# C-08_SODIMM.net
KiCad netlist of a schematic drawn in Altium Designer
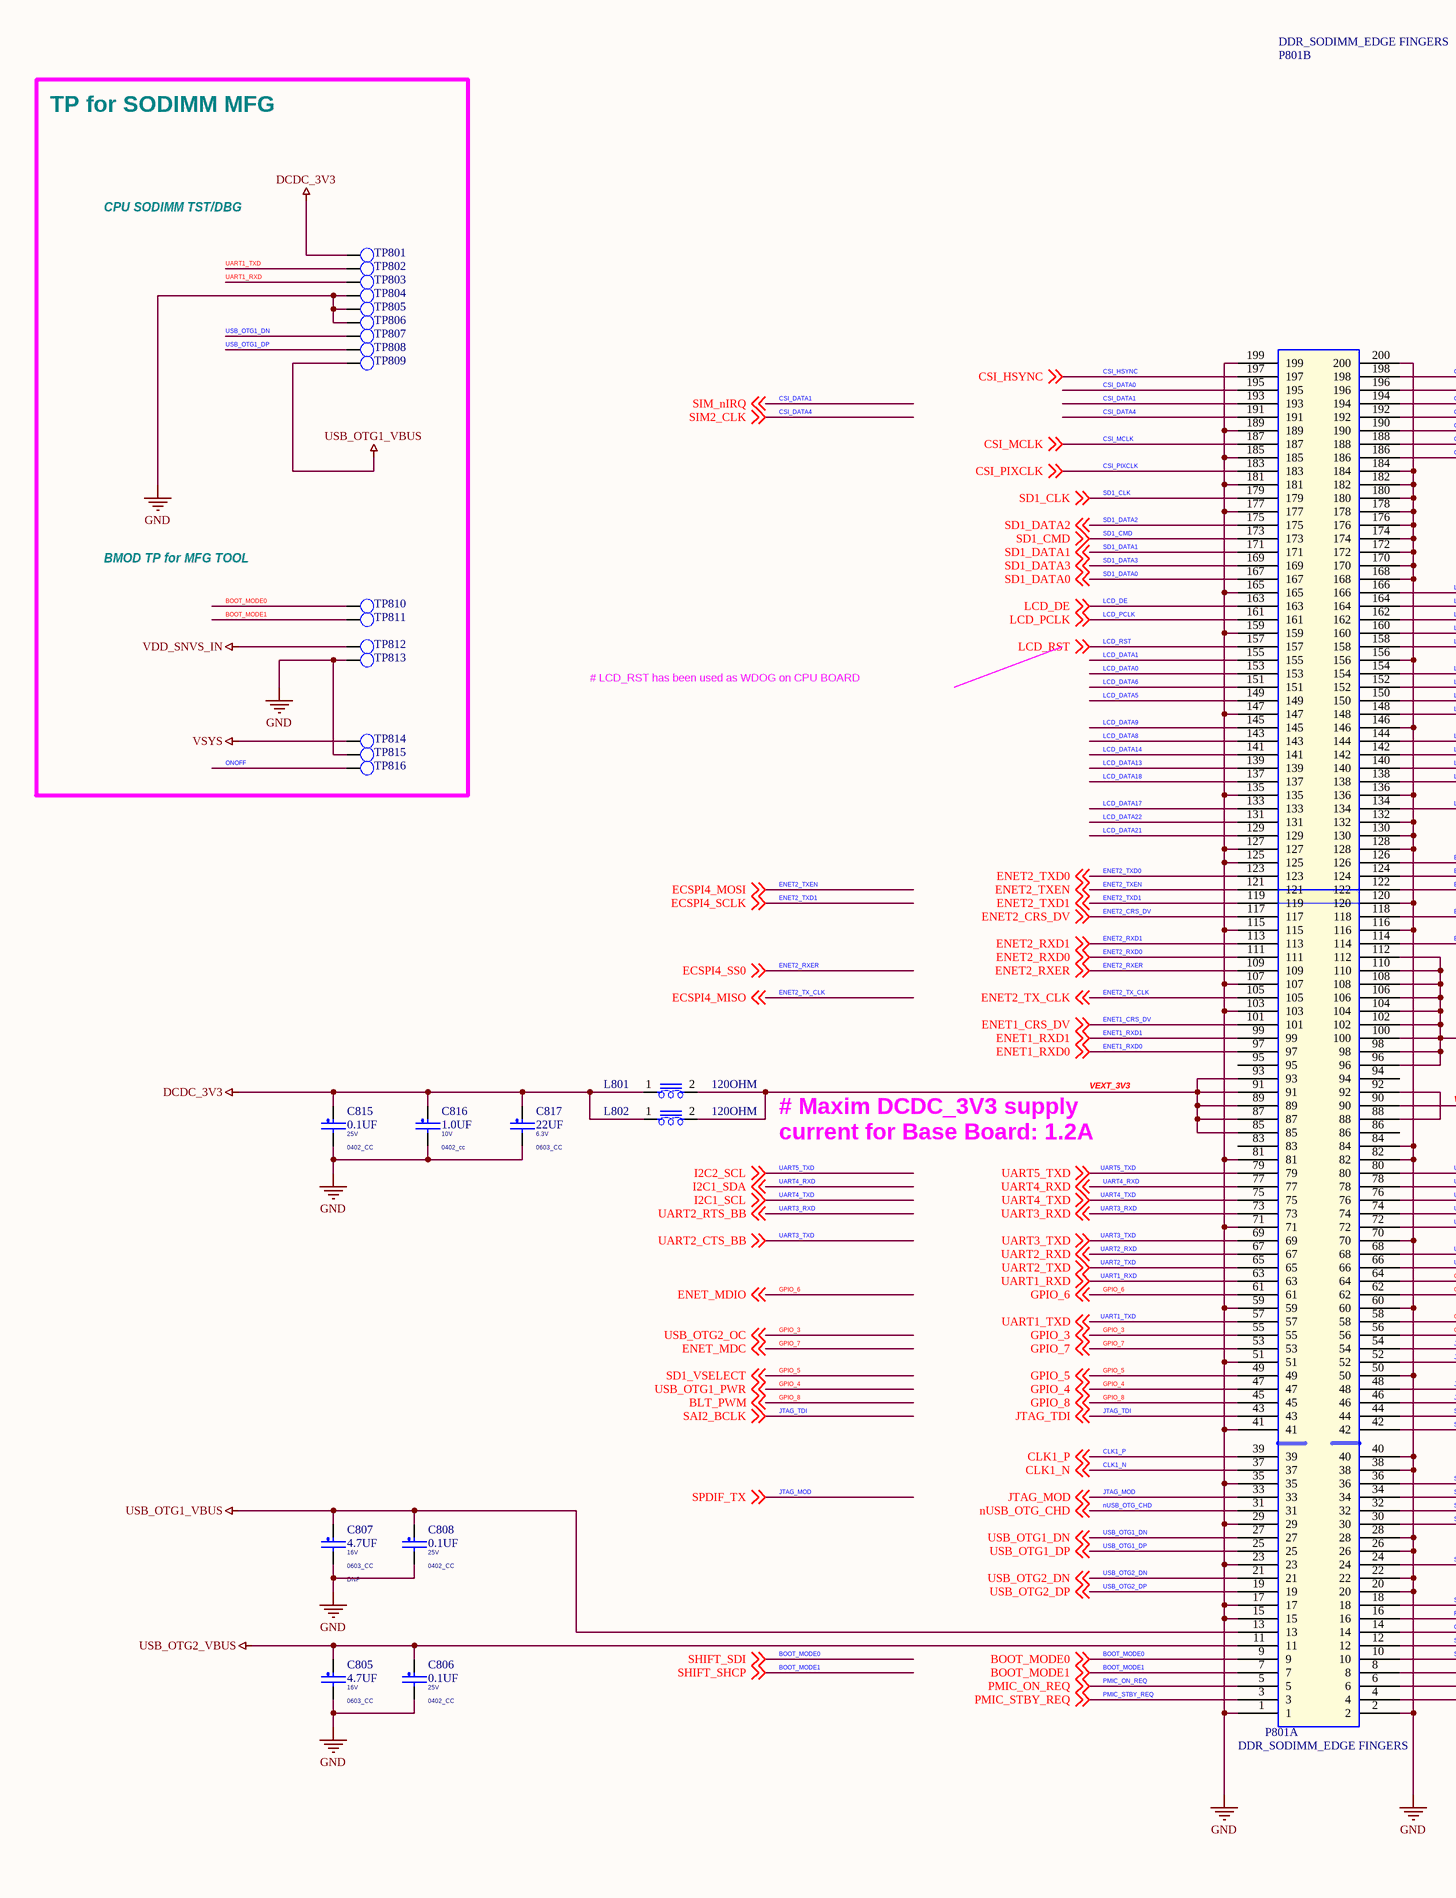
[diagram p0: C-08 SODIMM.SchDoc, left]
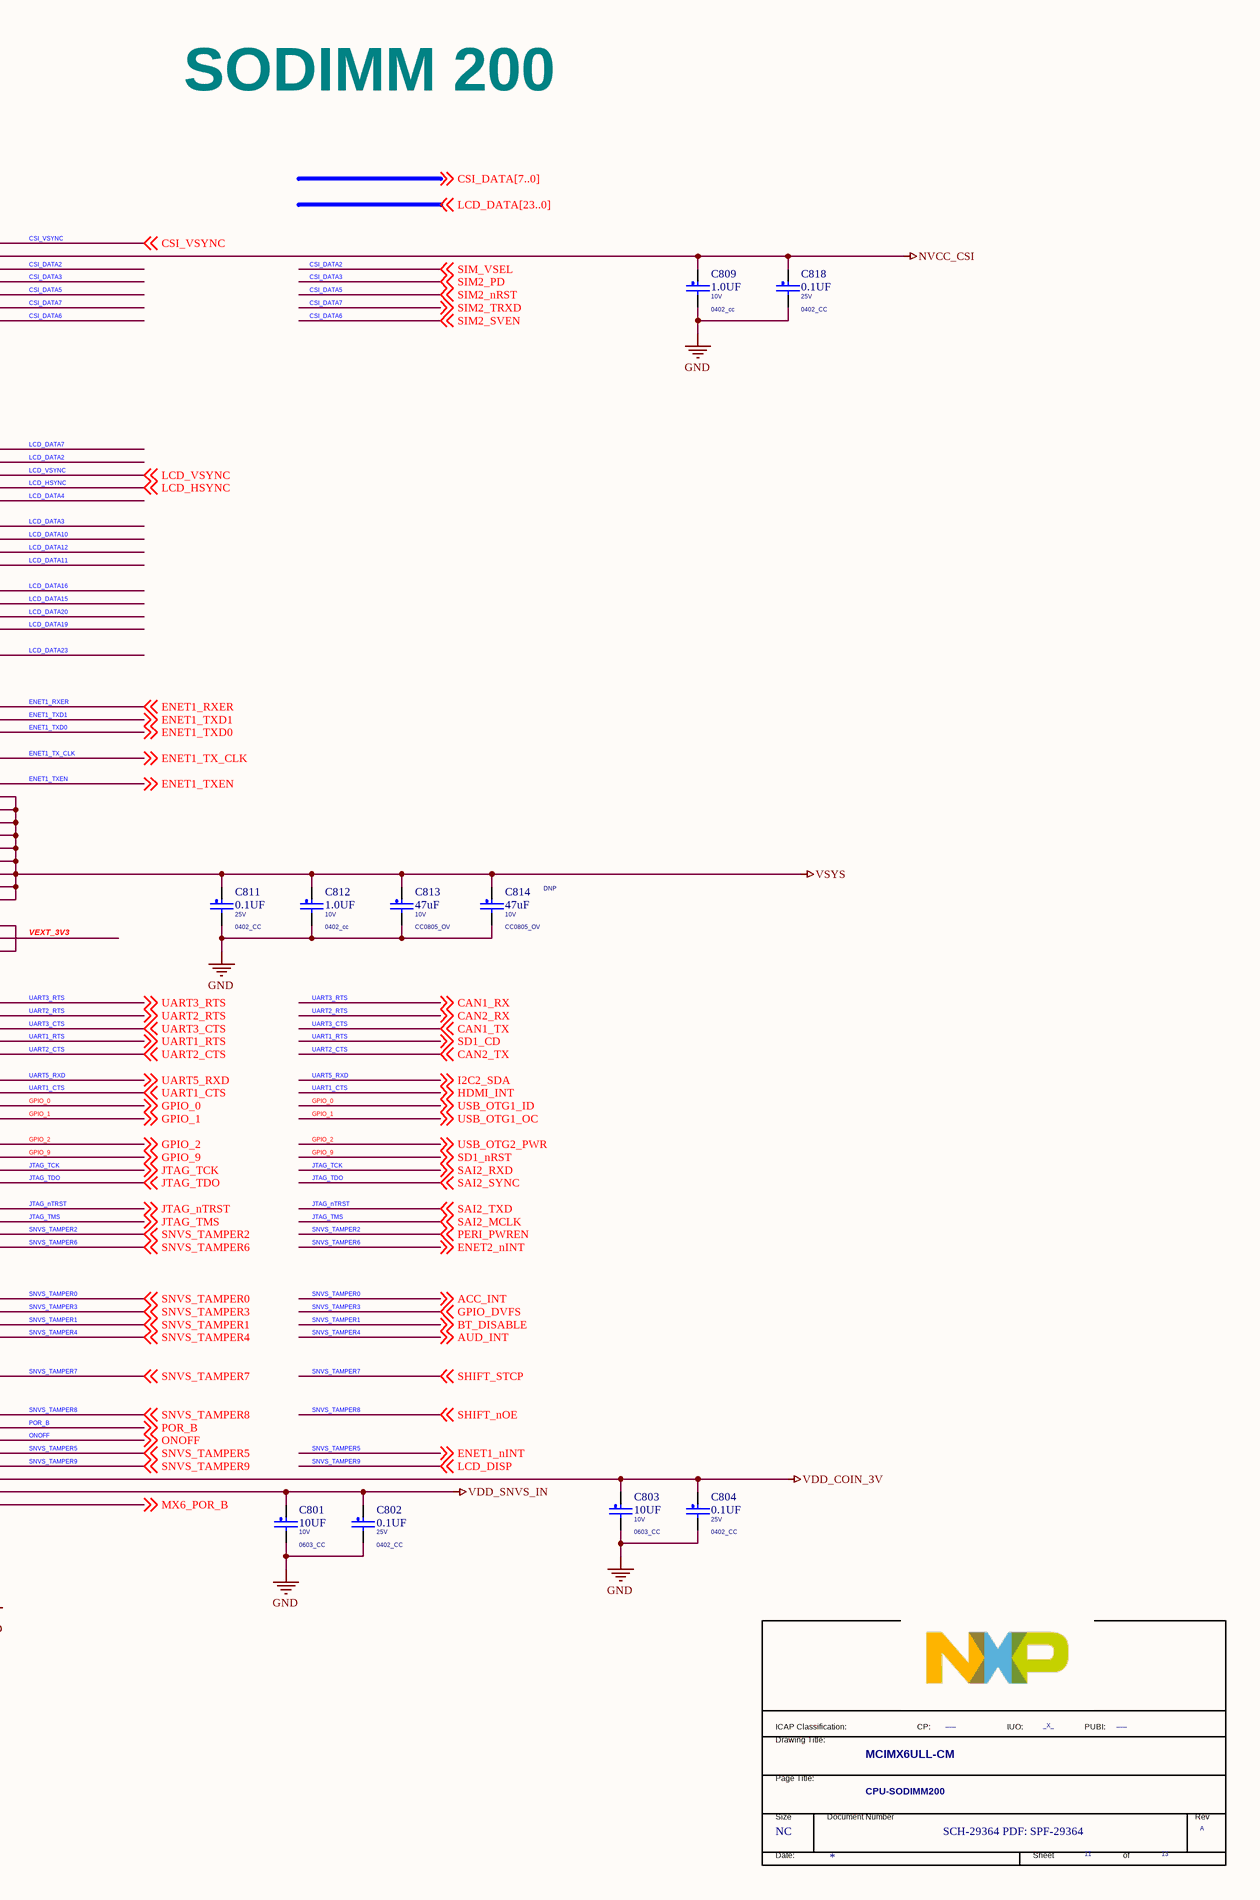
[diagram p1: C-08 SODIMM.SchDoc, right]

(export (version "E")
  (design (tool "Eeschema 10.0.6"))
  (components
    (comp (ref "*")
      (value "TitleBlock_FS")
      (fields
        (field (name "FIUO") "_X_")
        (field (name "PUBI") "___")
        (field (name "FCP") "___")
        (field (name "DOC") "SCH-29364 PDF: SPF-29364")
        (field (name "REVCODE") "A")
        (field (name "TITLE") "MCIMX6ULL-CM")
        (field (name "PAGE SIZE") "NC")
        (field (name "PAGE NUMBER") "11")
        (field (name "PAGE COUNT") "13")
        (field (name "PAGETITLE") "CPU-SODIMM200")
      )
      (libsource (lib "*") (part "TitleBlock_FS"))
    )
    (comp (ref "C801")
      (value "10UF")
      (footprint "C0603_H0.8mm_IPC_C")
      (description "CAP CER 10UF 10V 20% X5R 0603")
      (fields (field (name "VOLTAGE") "10V") (field (name "PCB FOOTPRINT") "0603_CC"))
      (libsource (lib "*") (part "CAP_NP"))
    )
    (comp (ref "C802")
      (value "0.1UF")
      (footprint "C0402_H0.5mm")
      (description "CAP CER 0.1UF 25V 10% X5R 0402")
      (fields
        (field (name "TOLERANCE") "10%")
        (field (name "VOLTAGE") "25V")
        (field (name "PCB FOOTPRINT") "0402_CC")
      )
      (libsource (lib "*") (part "CAP_NP"))
    )
    (comp (ref "C803")
      (value "10UF")
      (footprint "C0603_H0.8mm_IPC_C")
      (description "CAP CER 10UF 10V 20% X5R 0603")
      (fields (field (name "VOLTAGE") "10V") (field (name "PCB FOOTPRINT") "0603_CC"))
      (libsource (lib "*") (part "CAP_NP"))
    )
    (comp (ref "C804")
      (value "0.1UF")
      (footprint "C0402_H0.5mm")
      (description "CAP CER 0.1UF 25V 10% X5R 0402")
      (fields
        (field (name "TOLERANCE") "10%")
        (field (name "VOLTAGE") "25V")
        (field (name "PCB FOOTPRINT") "0402_CC")
      )
      (libsource (lib "*") (part "CAP_NP"))
    )
    (comp (ref "C805")
      (value "4.7UF")
      (footprint "C0603_H0.8mm_IPC_C")
      (description "CAP CER 4.7uF 16V 10% X5R 0603")
      (fields
        (field (name "TOLERANCE") "10%")
        (field (name "VOLTAGE") "16V")
        (field (name "PCB FOOTPRINT") "0603_CC")
      )
      (libsource (lib "*") (part "CAP_NP"))
    )
    (comp (ref "C806")
      (value "0.1UF")
      (footprint "C0402_H0.5mm")
      (description "CAP CER 0.1UF 25V 10% X5R 0402")
      (fields
        (field (name "TOLERANCE") "10%")
        (field (name "VOLTAGE") "25V")
        (field (name "PCB FOOTPRINT") "0402_CC")
      )
      (libsource (lib "*") (part "CAP_NP"))
    )
    (comp (ref "C807")
      (value "4.7UF")
      (footprint "C0603_H0.8mm_IPC_C")
      (description "CAP CER 4.7uF 16V 10% X5R 0603")
      (fields
        (field (name "PCB FOOTPRINT") "0603_CC")
        (field (name "VOLTAGE") "16V")
        (field (name "ASSY_OPT") "DNP")
        (field (name "TOLERANCE") "10%")
      )
      (libsource (lib "*") (part "CAP_NP"))
    )
    (comp (ref "C808")
      (value "0.1UF")
      (footprint "C0402_H0.5mm")
      (description "CAP CER 0.1UF 25V 10% X5R 0402")
      (fields
        (field (name "TOLERANCE") "10%")
        (field (name "VOLTAGE") "25V")
        (field (name "PCB FOOTPRINT") "0402_CC")
      )
      (libsource (lib "*") (part "CAP_NP"))
    )
    (comp (ref "C809")
      (value "1.0UF")
      (footprint "C0402_H0.5mm")
      (description "CAP CER 1.0UF 10V 10% X5R 0402")
      (fields (field (name "VOLTAGE") "10V") (field (name "PCB FOOTPRINT") "0402_cc"))
      (libsource (lib "*") (part "CAP_NP"))
    )
    (comp (ref "C811")
      (value "0.1UF")
      (footprint "C0402_H0.5mm")
      (description "CAP CER 0.1UF 25V 10% X5R 0402")
      (fields
        (field (name "VOLTAGE") "25V")
        (field (name "TOLERANCE") "10%")
        (field (name "PCB FOOTPRINT") "0402_CC")
      )
      (libsource (lib "*") (part "CAP_NP"))
    )
    (comp (ref "C812")
      (value "1.0UF")
      (footprint "C0402_H0.5mm")
      (description "CAP CER 1.0UF 10V 10% X5R 0402")
      (fields (field (name "VOLTAGE") "10V") (field (name "PCB FOOTPRINT") "0402_cc"))
      (libsource (lib "*") (part "CAP_NP"))
    )
    (comp (ref "C813")
      (value "47uF")
      (footprint "CC0805_OV")
      (description "CAP CER 47uF 10V 20% X5R 0805")
      (fields
        (field (name "VOLTAGE") "10V")
        (field (name "TOLERANCE") "20%")
        (field (name "PCB FOOTPRINT") "CC0805_OV")
      )
      (libsource (lib "*") (part "CAP_NP"))
    )
    (comp (ref "C814")
      (value "47uF")
      (footprint "CC0805_OV")
      (description "CAP CER 47uF 10V 20% X5R 0805")
      (fields
        (field (name "VOLTAGE") "10V")
        (field (name "ASSY_OPT") "DNP")
        (field (name "TOLERANCE") "20%")
        (field (name "PCB FOOTPRINT") "CC0805_OV")
      )
      (libsource (lib "*") (part "CAP_NP"))
    )
    (comp (ref "C815")
      (value "0.1UF")
      (footprint "C0402_H0.5mm")
      (description "CAP CER 0.1UF 25V 10% X5R 0402")
      (fields
        (field (name "VOLTAGE") "25V")
        (field (name "TOLERANCE") "10%")
        (field (name "PCB FOOTPRINT") "0402_CC")
      )
      (libsource (lib "*") (part "CAP_NP"))
    )
    (comp (ref "C816")
      (value "1.0UF")
      (footprint "C0402_H0.5mm")
      (description "CAP CER 1.0UF 10V 10% X5R 0402")
      (fields (field (name "VOLTAGE") "10V") (field (name "PCB FOOTPRINT") "0402_cc"))
      (libsource (lib "*") (part "CAP_NP"))
    )
    (comp (ref "C817")
      (value "22UF")
      (footprint "C0603_H0.8mm_IPC_C")
      (description "CAP CER 22UF 6.3V 20% X5R 0603")
      (fields
        (field (name "VOLTAGE") "6.3V")
        (field (name "TOLERANCE") "20%")
        (field (name "VOLTAGE RATING") "6.3V")
        (field (name "PCB FOOTPRINT") "0603_CC")
      )
      (libsource (lib "*") (part "CAP_NP"))
    )
    (comp (ref "C818")
      (value "0.1UF")
      (footprint "C0402_H0.5mm")
      (description "CAP CER 0.1UF 25V 10% X5R 0402")
      (fields
        (field (name "VOLTAGE") "25V")
        (field (name "TOLERANCE") "10%")
        (field (name "PCB FOOTPRINT") "0402_CC")
      )
      (libsource (lib "*") (part "CAP_NP"))
    )
    (comp (ref "L801")
      (value "120OHM")
      (footprint "0603_CC")
      (description "IND FER BEAD 120OHM@100MHZ 2A 25% 0603")
      (fields (field (name "TOLERANCE") "25%"))
      (libsource (lib "*") (part "BEAD_0"))
    )
    (comp (ref "L802")
      (value "120OHM")
      (footprint "0603_CC")
      (description "IND FER BEAD 120OHM@100MHZ 2A 25% 0603")
      (fields (field (name "TOLERANCE") "25%"))
      (libsource (lib "*") (part "BEAD_0"))
    )
    (comp (ref "P801")
      (value "DDR_SODIMM_EDGE FINGERS")
      (footprint "SODIMM_67589")
      (description "200 PIN SODIMM EDGE FINGERS -- AU FOOTPRINT ONLY, NO PART TO ORDER")
      (libsource (lib "*") (part "CONN_EDGE_200P"))
    )
    (comp (ref "TP801")
      (value "TP_35MIL")
      (footprint "testpoint_35mil")
      (description "TEST POINT PAD .035 SMT, no part to order")
      (libsource (lib "*") (part "T POINT R"))
    )
    (comp (ref "TP802")
      (value "TP_35MIL")
      (footprint "testpoint_35mil")
      (description "TEST POINT PAD .035 SMT, no part to order")
      (libsource (lib "*") (part "T POINT R"))
    )
    (comp (ref "TP803")
      (value "TP_35MIL")
      (footprint "testpoint_35mil")
      (description "TEST POINT PAD .035 SMT, no part to order")
      (libsource (lib "*") (part "T POINT R"))
    )
    (comp (ref "TP804")
      (value "TP_35MIL")
      (footprint "testpoint_35mil")
      (description "TEST POINT PAD .035 SMT, no part to order")
      (libsource (lib "*") (part "T POINT R"))
    )
    (comp (ref "TP805")
      (value "TP_35MIL")
      (footprint "testpoint_35mil")
      (description "TEST POINT PAD .035 SMT, no part to order")
      (libsource (lib "*") (part "T POINT R"))
    )
    (comp (ref "TP806")
      (value "TP_35MIL")
      (footprint "testpoint_35mil")
      (description "TEST POINT PAD .035 SMT, no part to order")
      (libsource (lib "*") (part "T POINT R"))
    )
    (comp (ref "TP807")
      (value "TP_35MIL")
      (footprint "testpoint_35mil")
      (description "TEST POINT PAD .035 SMT, no part to order")
      (libsource (lib "*") (part "T POINT R"))
    )
    (comp (ref "TP808")
      (value "TP_35MIL")
      (footprint "testpoint_35mil")
      (description "TEST POINT PAD .035 SMT, no part to order")
      (libsource (lib "*") (part "T POINT R"))
    )
    (comp (ref "TP809")
      (value "TP_35MIL")
      (footprint "testpoint_35mil")
      (description "TEST POINT PAD .035 SMT, no part to order")
      (libsource (lib "*") (part "T POINT R"))
    )
    (comp (ref "TP810")
      (value "TP_35MIL")
      (footprint "testpoint_35mil")
      (description "TEST POINT PAD .035 SMT, no part to order")
      (libsource (lib "*") (part "T POINT R"))
    )
    (comp (ref "TP811")
      (value "TP_35MIL")
      (footprint "testpoint_35mil")
      (description "TEST POINT PAD .035 SMT, no part to order")
      (libsource (lib "*") (part "T POINT R"))
    )
    (comp (ref "TP812")
      (value "TP_35MIL")
      (footprint "testpoint_35mil")
      (description "TEST POINT PAD .035 SMT, no part to order")
      (libsource (lib "*") (part "T POINT R"))
    )
    (comp (ref "TP813")
      (value "TP_35MIL")
      (footprint "testpoint_35mil")
      (description "TEST POINT PAD .035 SMT, no part to order")
      (libsource (lib "*") (part "T POINT R"))
    )
    (comp (ref "TP814")
      (value "TP_35MIL")
      (footprint "testpoint_35mil")
      (description "TEST POINT PAD .035 SMT, no part to order")
      (libsource (lib "*") (part "T POINT R"))
    )
    (comp (ref "TP815")
      (value "TP_35MIL")
      (footprint "testpoint_35mil")
      (description "TEST POINT PAD .035 SMT, no part to order")
      (libsource (lib "*") (part "T POINT R"))
    )
    (comp (ref "TP816")
      (value "TP_35MIL")
      (footprint "testpoint_35mil")
      (description "TEST POINT PAD .035 SMT, no part to order")
      (libsource (lib "*") (part "T POINT R"))
    )
  )
  (nets
    (net (code "1") (name "/VEXT_3V3") (class "Default")
      (node (ref "L801") (pin "2") (pinfunction "2_2") (pintype "passive"))
      (node (ref "L802") (pin "2") (pinfunction "2_2") (pintype "passive"))
      (node (ref "P801") (pin "85") (pinfunction "85_85") (pintype "passive"))
      (node (ref "P801") (pin "87") (pinfunction "87_87") (pintype "passive"))
      (node (ref "P801") (pin "89") (pinfunction "89_89") (pintype "passive"))
      (node (ref "P801") (pin "90") (pinfunction "90_90") (pintype "passive"))
      (node (ref "P801") (pin "91") (pinfunction "91_91") (pintype "passive"))
      (node (ref "P801") (pin "93") (pinfunction "93_93") (pintype "passive"))
    )
    (net (code "2") (name "ACC_INT") (class "Default")
      (node (ref "P801") (pin "36") (pinfunction "36_36") (pintype "passive"))
    )
    (net (code "3") (name "AUD_INT") (class "Default")
      (node (ref "P801") (pin "30") (pinfunction "30_30") (pintype "passive"))
    )
    (net (code "4") (name "BLT_PWM") (class "Default")
      (node (ref "P801") (pin "45") (pinfunction "45_45") (pintype "passive"))
    )
    (net (code "5") (name "BOOT_MODE0") (class "Default")
      (node (ref "P801") (pin "9") (pinfunction "9_9") (pintype "passive"))
      (node (ref "TP810") (pin "1") (pinfunction "TP_1") (pintype "passive"))
    )
    (net (code "6") (name "BOOT_MODE1") (class "Default")
      (node (ref "P801") (pin "7") (pinfunction "7_7") (pintype "passive"))
      (node (ref "TP811") (pin "1") (pinfunction "TP_1") (pintype "passive"))
    )
    (net (code "7") (name "BT_DISABLE") (class "Default")
      (node (ref "P801") (pin "32") (pinfunction "32_32") (pintype "passive"))
    )
    (net (code "8") (name "CAN1_RX") (class "Default")
      (node (ref "P801") (pin "80") (pinfunction "80_80") (pintype "passive"))
    )
    (net (code "9") (name "CAN1_TX") (class "Default")
      (node (ref "P801") (pin "76") (pinfunction "76_76") (pintype "passive"))
    )
    (net (code "10") (name "CAN2_RX") (class "Default")
      (node (ref "P801") (pin "78") (pinfunction "78_78") (pintype "passive"))
    )
    (net (code "11") (name "CAN2_TX") (class "Default")
      (node (ref "P801") (pin "72") (pinfunction "72_72") (pintype "passive"))
    )
    (net (code "12") (name "CLK1_N") (class "Default")
      (node (ref "P801") (pin "37") (pinfunction "37_37") (pintype "passive"))
    )
    (net (code "13") (name "CLK1_P") (class "Default")
      (node (ref "P801") (pin "39") (pinfunction "39_39") (pintype "passive"))
    )
    (net (code "14") (name "CSI_DATA0") (class "Default")
      (node (ref "P801") (pin "195") (pinfunction "195_195") (pintype "passive"))
    )
    (net (code "16") (name "CSI_HSYNC") (class "Default")
      (node (ref "P801") (pin "197") (pinfunction "197_197") (pintype "passive"))
    )
    (net (code "17") (name "CSI_MCLK") (class "Default")
      (node (ref "P801") (pin "187") (pinfunction "187_187") (pintype "passive"))
    )
    (net (code "18") (name "CSI_PIXCLK") (class "Default")
      (node (ref "P801") (pin "183") (pinfunction "183_183") (pintype "passive"))
    )
    (net (code "19") (name "CSI_VSYNC") (class "Default")
      (node (ref "P801") (pin "198") (pinfunction "198_198") (pintype "passive"))
    )
    (net (code "20") (name "DCDC_3V3") (class "Default")
      (node (ref "C815") (pin "1") (pinfunction "1_1") (pintype "passive"))
      (node (ref "C816") (pin "1") (pinfunction "1_1") (pintype "passive"))
      (node (ref "C817") (pin "1") (pinfunction "1_1") (pintype "passive"))
      (node (ref "L801") (pin "1") (pinfunction "1_1") (pintype "passive"))
      (node (ref "L802") (pin "1") (pinfunction "1_1") (pintype "passive"))
      (node (ref "TP801") (pin "1") (pinfunction "TP_1") (pintype "passive"))
    )
    (net (code "21") (name "ECSPI4_MISO") (class "Default")
      (node (ref "P801") (pin "105") (pinfunction "105_105") (pintype "passive"))
    )
    (net (code "22") (name "ECSPI4_MOSI") (class "Default")
      (node (ref "P801") (pin "121") (pinfunction "121_121") (pintype "passive"))
    )
    (net (code "23") (name "ECSPI4_SCLK") (class "Default")
      (node (ref "P801") (pin "119") (pinfunction "119_119") (pintype "passive"))
    )
    (net (code "24") (name "ECSPI4_SS0") (class "Default")
      (node (ref "P801") (pin "109") (pinfunction "109_109") (pintype "passive"))
    )
    (net (code "25") (name "ENET1_CRS_DV") (class "Default")
      (node (ref "P801") (pin "101") (pinfunction "101_101") (pintype "passive"))
    )
    (net (code "26") (name "ENET1_RXD0") (class "Default")
      (node (ref "P801") (pin "97") (pinfunction "97_97") (pintype "passive"))
    )
    (net (code "27") (name "ENET1_RXD1") (class "Default")
      (node (ref "P801") (pin "99") (pinfunction "99_99") (pintype "passive"))
    )
    (net (code "28") (name "ENET1_RXER") (class "Default")
      (node (ref "P801") (pin "126") (pinfunction "126_126") (pintype "passive"))
    )
    (net (code "29") (name "ENET1_TXD0") (class "Default")
      (node (ref "P801") (pin "122") (pinfunction "122_122") (pintype "passive"))
    )
    (net (code "30") (name "ENET1_TXD1") (class "Default")
      (node (ref "P801") (pin "124") (pinfunction "124_124") (pintype "passive"))
    )
    (net (code "31") (name "ENET1_TXEN") (class "Default")
      (node (ref "P801") (pin "114") (pinfunction "114_114") (pintype "passive"))
    )
    (net (code "32") (name "ENET1_TX_CLK") (class "Default")
      (node (ref "P801") (pin "118") (pinfunction "118_118") (pintype "passive"))
    )
    (net (code "33") (name "ENET1_nINT") (class "Default")
      (node (ref "P801") (pin "12") (pinfunction "12_12") (pintype "passive"))
    )
    (net (code "34") (name "ENET2_CRS_DV") (class "Default")
      (node (ref "P801") (pin "117") (pinfunction "117_117") (pintype "passive"))
    )
    (net (code "35") (name "ENET2_RXD0") (class "Default")
      (node (ref "P801") (pin "111") (pinfunction "111_111") (pintype "passive"))
    )
    (net (code "36") (name "ENET2_RXD1") (class "Default")
      (node (ref "P801") (pin "113") (pinfunction "113_113") (pintype "passive"))
    )
    (net (code "37") (name "ENET2_TXD0") (class "Default")
      (node (ref "P801") (pin "123") (pinfunction "123_123") (pintype "passive"))
    )
    (net (code "38") (name "ENET2_nINT") (class "Default")
      (node (ref "P801") (pin "42") (pinfunction "42_42") (pintype "passive"))
    )
    (net (code "39") (name "ENET_MDC") (class "Default")
      (node (ref "P801") (pin "53") (pinfunction "53_53") (pintype "passive"))
    )
    (net (code "40") (name "ENET_MDIO") (class "Default")
      (node (ref "P801") (pin "61") (pinfunction "61_61") (pintype "passive"))
    )
    (net (code "41") (name "GND") (class "Default")
      (node (ref "C801") (pin "2") (pinfunction "2_2") (pintype "passive"))
      (node (ref "C802") (pin "2") (pinfunction "2_2") (pintype "passive"))
      (node (ref "C803") (pin "2") (pinfunction "2_2") (pintype "passive"))
      (node (ref "C804") (pin "2") (pinfunction "2_2") (pintype "passive"))
      (node (ref "C805") (pin "2") (pinfunction "2_2") (pintype "passive"))
      (node (ref "C806") (pin "2") (pinfunction "2_2") (pintype "passive"))
      (node (ref "C807") (pin "2") (pinfunction "2_2") (pintype "passive"))
      (node (ref "C808") (pin "2") (pinfunction "2_2") (pintype "passive"))
      (node (ref "C809") (pin "2") (pinfunction "2_2") (pintype "passive"))
      (node (ref "C811") (pin "2") (pinfunction "2_2") (pintype "passive"))
      (node (ref "C812") (pin "2") (pinfunction "2_2") (pintype "passive"))
      (node (ref "C813") (pin "2") (pinfunction "2_2") (pintype "passive"))
      (node (ref "C814") (pin "2") (pinfunction "2_2") (pintype "passive"))
      (node (ref "C815") (pin "2") (pinfunction "2_2") (pintype "passive"))
      (node (ref "C816") (pin "2") (pinfunction "2_2") (pintype "passive"))
      (node (ref "C817") (pin "2") (pinfunction "2_2") (pintype "passive"))
      (node (ref "C818") (pin "2") (pinfunction "2_2") (pintype "passive"))
      (node (ref "P801") (pin "1") (pinfunction "1_1") (pintype "passive"))
      (node (ref "P801") (pin "103") (pinfunction "103_103") (pintype "passive"))
      (node (ref "P801") (pin "107") (pinfunction "107_107") (pintype "passive"))
      (node (ref "P801") (pin "115") (pinfunction "115_115") (pintype "passive"))
      (node (ref "P801") (pin "116") (pinfunction "116_116") (pintype "passive"))
      (node (ref "P801") (pin "120") (pinfunction "120_120") (pintype "passive"))
      (node (ref "P801") (pin "125") (pinfunction "125_125") (pintype "passive"))
      (node (ref "P801") (pin "127") (pinfunction "127_127") (pintype "passive"))
      (node (ref "P801") (pin "128") (pinfunction "128_128") (pintype "passive"))
      (node (ref "P801") (pin "130") (pinfunction "130_130") (pintype "passive"))
      (node (ref "P801") (pin "132") (pinfunction "132_132") (pintype "passive"))
      (node (ref "P801") (pin "135") (pinfunction "135_135") (pintype "passive"))
      (node (ref "P801") (pin "136") (pinfunction "136_136") (pintype "passive"))
      (node (ref "P801") (pin "146") (pinfunction "146_146") (pintype "passive"))
      (node (ref "P801") (pin "147") (pinfunction "147_147") (pintype "passive"))
      (node (ref "P801") (pin "15") (pinfunction "15_15") (pintype "passive"))
      (node (ref "P801") (pin "156") (pinfunction "156_156") (pintype "passive"))
      (node (ref "P801") (pin "159") (pinfunction "159_159") (pintype "passive"))
      (node (ref "P801") (pin "165") (pinfunction "165_165") (pintype "passive"))
      (node (ref "P801") (pin "168") (pinfunction "168_168") (pintype "passive"))
      (node (ref "P801") (pin "17") (pinfunction "17_17") (pintype "passive"))
      (node (ref "P801") (pin "170") (pinfunction "170_170") (pintype "passive"))
      (node (ref "P801") (pin "172") (pinfunction "172_172") (pintype "passive"))
      (node (ref "P801") (pin "174") (pinfunction "174_174") (pintype "passive"))
      (node (ref "P801") (pin "176") (pinfunction "176_176") (pintype "passive"))
      (node (ref "P801") (pin "177") (pinfunction "177_177") (pintype "passive"))
      (node (ref "P801") (pin "178") (pinfunction "178_178") (pintype "passive"))
      (node (ref "P801") (pin "180") (pinfunction "180_180") (pintype "passive"))
      (node (ref "P801") (pin "181") (pinfunction "181_181") (pintype "passive"))
      (node (ref "P801") (pin "182") (pinfunction "182_182") (pintype "passive"))
      (node (ref "P801") (pin "184") (pinfunction "184_184") (pintype "passive"))
      (node (ref "P801") (pin "185") (pinfunction "185_185") (pintype "passive"))
      (node (ref "P801") (pin "189") (pinfunction "189_189") (pintype "passive"))
      (node (ref "P801") (pin "199") (pinfunction "199_199") (pintype "passive"))
      (node (ref "P801") (pin "2") (pinfunction "2_2") (pintype "passive"))
      (node (ref "P801") (pin "20") (pinfunction "20_20") (pintype "passive"))
      (node (ref "P801") (pin "200") (pinfunction "200_200") (pintype "passive"))
      (node (ref "P801") (pin "22") (pinfunction "22_22") (pintype "passive"))
      (node (ref "P801") (pin "23") (pinfunction "23_23") (pintype "passive"))
      (node (ref "P801") (pin "26") (pinfunction "26_26") (pintype "passive"))
      (node (ref "P801") (pin "28") (pinfunction "28_28") (pintype "passive"))
      (node (ref "P801") (pin "29") (pinfunction "29_29") (pintype "passive"))
      (node (ref "P801") (pin "35") (pinfunction "35_35") (pintype "passive"))
      (node (ref "P801") (pin "38") (pinfunction "38_38") (pintype "passive"))
      (node (ref "P801") (pin "40") (pinfunction "40_40") (pintype "passive"))
      (node (ref "P801") (pin "41") (pinfunction "41_41") (pintype "passive"))
      (node (ref "P801") (pin "50") (pinfunction "50_50") (pintype "passive"))
      (node (ref "P801") (pin "51") (pinfunction "51_51") (pintype "passive"))
      (node (ref "P801") (pin "59") (pinfunction "59_59") (pintype "passive"))
      (node (ref "P801") (pin "60") (pinfunction "60_60") (pintype "passive"))
      (node (ref "P801") (pin "70") (pinfunction "70_70") (pintype "passive"))
      (node (ref "P801") (pin "71") (pinfunction "71_71") (pintype "passive"))
      (node (ref "P801") (pin "81") (pinfunction "81_81") (pintype "passive"))
      (node (ref "P801") (pin "82") (pinfunction "82_82") (pintype "passive"))
      (node (ref "P801") (pin "84") (pinfunction "84_84") (pintype "passive"))
      (node (ref "TP804") (pin "1") (pinfunction "TP_1") (pintype "passive"))
      (node (ref "TP805") (pin "1") (pinfunction "TP_1") (pintype "passive"))
      (node (ref "TP806") (pin "1") (pinfunction "TP_1") (pintype "passive"))
      (node (ref "TP813") (pin "1") (pinfunction "TP_1") (pintype "passive"))
      (node (ref "TP815") (pin "1") (pinfunction "TP_1") (pintype "passive"))
    )
    (net (code "42") (name "GPIO_0") (class "Default")
      (node (ref "P801") (pin "64") (pinfunction "64_64") (pintype "passive"))
    )
    (net (code "43") (name "GPIO_1") (class "Default")
      (node (ref "P801") (pin "62") (pinfunction "62_62") (pintype "passive"))
    )
    (net (code "44") (name "GPIO_2") (class "Default")
      (node (ref "P801") (pin "58") (pinfunction "58_58") (pintype "passive"))
    )
    (net (code "45") (name "GPIO_3") (class "Default")
      (node (ref "P801") (pin "55") (pinfunction "55_55") (pintype "passive"))
    )
    (net (code "46") (name "GPIO_4") (class "Default")
      (node (ref "P801") (pin "47") (pinfunction "47_47") (pintype "passive"))
    )
    (net (code "47") (name "GPIO_5") (class "Default")
      (node (ref "P801") (pin "49") (pinfunction "49_49") (pintype "passive"))
    )
    (net (code "48") (name "GPIO_9") (class "Default")
      (node (ref "P801") (pin "56") (pinfunction "56_56") (pintype "passive"))
    )
    (net (code "49") (name "GPIO_DVFS") (class "Default")
      (node (ref "P801") (pin "34") (pinfunction "34_34") (pintype "passive"))
    )
    (net (code "50") (name "HDMI_INT") (class "Default")
      (node (ref "P801") (pin "66") (pinfunction "66_66") (pintype "passive"))
    )
    (net (code "51") (name "I2C1_SCL") (class "Default")
      (node (ref "P801") (pin "75") (pinfunction "75_75") (pintype "passive"))
    )
    (net (code "52") (name "I2C1_SDA") (class "Default")
      (node (ref "P801") (pin "77") (pinfunction "77_77") (pintype "passive"))
    )
    (net (code "53") (name "I2C2_SCL") (class "Default")
      (node (ref "P801") (pin "79") (pinfunction "79_79") (pintype "passive"))
    )
    (net (code "54") (name "I2C2_SDA") (class "Default")
      (node (ref "P801") (pin "68") (pinfunction "68_68") (pintype "passive"))
    )
    (net (code "55") (name "JTAG_MOD") (class "Default")
      (node (ref "P801") (pin "33") (pinfunction "33_33") (pintype "passive"))
    )
    (net (code "56") (name "JTAG_TCK") (class "Default")
      (node (ref "P801") (pin "54") (pinfunction "54_54") (pintype "passive"))
    )
    (net (code "57") (name "JTAG_TDI") (class "Default")
      (node (ref "P801") (pin "43") (pinfunction "43_43") (pintype "passive"))
    )
    (net (code "58") (name "JTAG_TDO") (class "Default")
      (node (ref "P801") (pin "52") (pinfunction "52_52") (pintype "passive"))
    )
    (net (code "59") (name "JTAG_TMS") (class "Default")
      (node (ref "P801") (pin "46") (pinfunction "46_46") (pintype "passive"))
    )
    (net (code "60") (name "JTAG_nTRST") (class "Default")
      (node (ref "P801") (pin "48") (pinfunction "48_48") (pintype "passive"))
    )
    (net (code "61") (name "LCD_DATA0") (class "Default")
      (node (ref "P801") (pin "153") (pinfunction "153_153") (pintype "passive"))
    )
    (net (code "62") (name "LCD_DATA1") (class "Default")
      (node (ref "P801") (pin "155") (pinfunction "155_155") (pintype "passive"))
    )
    (net (code "63") (name "LCD_DATA2") (class "Default")
      (node (ref "P801") (pin "164") (pinfunction "164_164") (pintype "passive"))
    )
    (net (code "64") (name "LCD_DATA3") (class "Default")
      (node (ref "P801") (pin "154") (pinfunction "154_154") (pintype "passive"))
    )
    (net (code "65") (name "LCD_DATA4") (class "Default")
      (node (ref "P801") (pin "158") (pinfunction "158_158") (pintype "passive"))
    )
    (net (code "66") (name "LCD_DATA5") (class "Default")
      (node (ref "P801") (pin "149") (pinfunction "149_149") (pintype "passive"))
    )
    (net (code "67") (name "LCD_DATA6") (class "Default")
      (node (ref "P801") (pin "151") (pinfunction "151_151") (pintype "passive"))
    )
    (net (code "68") (name "LCD_DATA7") (class "Default")
      (node (ref "P801") (pin "166") (pinfunction "166_166") (pintype "passive"))
    )
    (net (code "69") (name "LCD_DATA8") (class "Default")
      (node (ref "P801") (pin "143") (pinfunction "143_143") (pintype "passive"))
    )
    (net (code "70") (name "LCD_DATA9") (class "Default")
      (node (ref "P801") (pin "145") (pinfunction "145_145") (pintype "passive"))
    )
    (net (code "71") (name "LCD_DATA10") (class "Default")
      (node (ref "P801") (pin "152") (pinfunction "152_152") (pintype "passive"))
    )
    (net (code "72") (name "LCD_DATA11") (class "Default")
      (node (ref "P801") (pin "148") (pinfunction "148_148") (pintype "passive"))
    )
    (net (code "73") (name "LCD_DATA12") (class "Default")
      (node (ref "P801") (pin "150") (pinfunction "150_150") (pintype "passive"))
    )
    (net (code "74") (name "LCD_DATA13") (class "Default")
      (node (ref "P801") (pin "139") (pinfunction "139_139") (pintype "passive"))
    )
    (net (code "75") (name "LCD_DATA14") (class "Default")
      (node (ref "P801") (pin "141") (pinfunction "141_141") (pintype "passive"))
    )
    (net (code "76") (name "LCD_DATA15") (class "Default")
      (node (ref "P801") (pin "142") (pinfunction "142_142") (pintype "passive"))
    )
    (net (code "77") (name "LCD_DATA16") (class "Default")
      (node (ref "P801") (pin "144") (pinfunction "144_144") (pintype "passive"))
    )
    (net (code "78") (name "LCD_DATA17") (class "Default")
      (node (ref "P801") (pin "133") (pinfunction "133_133") (pintype "passive"))
    )
    (net (code "79") (name "LCD_DATA18") (class "Default")
      (node (ref "P801") (pin "137") (pinfunction "137_137") (pintype "passive"))
    )
    (net (code "80") (name "LCD_DATA19") (class "Default")
      (node (ref "P801") (pin "138") (pinfunction "138_138") (pintype "passive"))
    )
    (net (code "81") (name "LCD_DATA20") (class "Default")
      (node (ref "P801") (pin "140") (pinfunction "140_140") (pintype "passive"))
    )
    (net (code "82") (name "LCD_DATA21") (class "Default")
      (node (ref "P801") (pin "129") (pinfunction "129_129") (pintype "passive"))
    )
    (net (code "83") (name "LCD_DATA22") (class "Default")
      (node (ref "P801") (pin "131") (pinfunction "131_131") (pintype "passive"))
    )
    (net (code "84") (name "LCD_DATA23") (class "Default")
      (node (ref "P801") (pin "134") (pinfunction "134_134") (pintype "passive"))
    )
    (net (code "86") (name "LCD_DE") (class "Default")
      (node (ref "P801") (pin "163") (pinfunction "163_163") (pintype "passive"))
    )
    (net (code "87") (name "LCD_DISP") (class "Default")
      (node (ref "P801") (pin "10") (pinfunction "10_10") (pintype "passive"))
    )
    (net (code "88") (name "LCD_HSYNC") (class "Default")
      (node (ref "P801") (pin "160") (pinfunction "160_160") (pintype "passive"))
    )
    (net (code "89") (name "LCD_PCLK") (class "Default")
      (node (ref "P801") (pin "161") (pinfunction "161_161") (pintype "passive"))
    )
    (net (code "90") (name "LCD_RST") (class "Default")
      (node (ref "P801") (pin "157") (pinfunction "157_157") (pintype "passive"))
    )
    (net (code "91") (name "LCD_VSYNC") (class "Default")
      (node (ref "P801") (pin "162") (pinfunction "162_162") (pintype "passive"))
    )
    (net (code "92") (name "MX6_POR_B") (class "Default")
      (node (ref "P801") (pin "4") (pinfunction "4_4") (pintype "passive"))
    )
    (net (code "93") (name "NVCC_CSI") (class "Default")
      (node (ref "C809") (pin "1") (pinfunction "1_1") (pintype "passive"))
      (node (ref "C818") (pin "1") (pinfunction "1_1") (pintype "passive"))
      (node (ref "P801") (pin "196") (pinfunction "196_196") (pintype "passive"))
    )
    (net (code "94") (name "Net-(P801-Pad88)") (class "Default")
      (node (ref "P801") (pin "88") (pinfunction "88_88") (pintype "passive"))
      (node (ref "P801") (pin "92") (pinfunction "92_92") (pintype "passive"))
    )
    (net (code "95") (name "ONOFF") (class "Default")
      (node (ref "P801") (pin "14") (pinfunction "14_14") (pintype "passive"))
      (node (ref "TP816") (pin "1") (pinfunction "TP_1") (pintype "passive"))
    )
    (net (code "96") (name "PERI_PWREN") (class "Default")
      (node (ref "P801") (pin "44") (pinfunction "44_44") (pintype "passive"))
    )
    (net (code "97") (name "PMIC_ON_REQ") (class "Default")
      (node (ref "P801") (pin "5") (pinfunction "5_5") (pintype "passive"))
    )
    (net (code "98") (name "PMIC_STBY_REQ") (class "Default")
      (node (ref "P801") (pin "3") (pinfunction "3_3") (pintype "passive"))
    )
    (net (code "99") (name "POR_B") (class "Default")
      (node (ref "P801") (pin "16") (pinfunction "16_16") (pintype "passive"))
    )
    (net (code "100") (name "SD1_CD") (class "Default")
      (node (ref "P801") (pin "74") (pinfunction "74_74") (pintype "passive"))
    )
    (net (code "101") (name "SD1_CLK") (class "Default")
      (node (ref "P801") (pin "179") (pinfunction "179_179") (pintype "passive"))
    )
    (net (code "102") (name "SD1_CMD") (class "Default")
      (node (ref "P801") (pin "173") (pinfunction "173_173") (pintype "passive"))
    )
    (net (code "103") (name "SD1_DATA0") (class "Default")
      (node (ref "P801") (pin "167") (pinfunction "167_167") (pintype "passive"))
    )
    (net (code "104") (name "SD1_DATA1") (class "Default")
      (node (ref "P801") (pin "171") (pinfunction "171_171") (pintype "passive"))
    )
    (net (code "105") (name "SD1_DATA2") (class "Default")
      (node (ref "P801") (pin "175") (pinfunction "175_175") (pintype "passive"))
    )
    (net (code "106") (name "SD1_DATA3") (class "Default")
      (node (ref "P801") (pin "169") (pinfunction "169_169") (pintype "passive"))
    )
    (net (code "107") (name "SHIFT_STCP") (class "Default")
      (node (ref "P801") (pin "24") (pinfunction "24_24") (pintype "passive"))
    )
    (net (code "108") (name "SHIFT_nOE") (class "Default")
      (node (ref "P801") (pin "18") (pinfunction "18_18") (pintype "passive"))
    )
    (net (code "109") (name "SIM2_CLK") (class "Default")
      (node (ref "P801") (pin "191") (pinfunction "191_191") (pintype "passive"))
    )
    (net (code "110") (name "SIM2_PD") (class "Default")
      (node (ref "P801") (pin "192") (pinfunction "192_192") (pintype "passive"))
    )
    (net (code "111") (name "SIM2_SVEN") (class "Default")
      (node (ref "P801") (pin "186") (pinfunction "186_186") (pintype "passive"))
    )
    (net (code "112") (name "SIM2_TRXD") (class "Default")
      (node (ref "P801") (pin "188") (pinfunction "188_188") (pintype "passive"))
    )
    (net (code "113") (name "SIM2_nRST") (class "Default")
      (node (ref "P801") (pin "190") (pinfunction "190_190") (pintype "passive"))
    )
    (net (code "114") (name "SIM_VSEL") (class "Default")
      (node (ref "P801") (pin "194") (pinfunction "194_194") (pintype "passive"))
    )
    (net (code "115") (name "SIM_nIRQ") (class "Default")
      (node (ref "P801") (pin "193") (pinfunction "193_193") (pintype "passive"))
    )
    (net (code "116") (name "UART1_RXD") (class "Default")
      (node (ref "P801") (pin "63") (pinfunction "63_63") (pintype "passive"))
      (node (ref "TP803") (pin "1") (pinfunction "TP_1") (pintype "passive"))
    )
    (net (code "117") (name "UART1_TXD") (class "Default")
      (node (ref "P801") (pin "57") (pinfunction "57_57") (pintype "passive"))
      (node (ref "TP802") (pin "1") (pinfunction "TP_1") (pintype "passive"))
    )
    (net (code "118") (name "UART2_CTS_BB") (class "Default")
      (node (ref "P801") (pin "69") (pinfunction "69_69") (pintype "passive"))
    )
    (net (code "119") (name "UART2_RTS_BB") (class "Default")
      (node (ref "P801") (pin "73") (pinfunction "73_73") (pintype "passive"))
    )
    (net (code "120") (name "UART2_RXD") (class "Default")
      (node (ref "P801") (pin "67") (pinfunction "67_67") (pintype "passive"))
    )
    (net (code "121") (name "UART2_TXD") (class "Default")
      (node (ref "P801") (pin "65") (pinfunction "65_65") (pintype "passive"))
    )
    (net (code "122") (name "USB_OTG1_DN") (class "Default")
      (node (ref "P801") (pin "27") (pinfunction "27_27") (pintype "passive"))
      (node (ref "TP807") (pin "1") (pinfunction "TP_1") (pintype "passive"))
    )
    (net (code "123") (name "USB_OTG1_DP") (class "Default")
      (node (ref "P801") (pin "25") (pinfunction "25_25") (pintype "passive"))
      (node (ref "TP808") (pin "1") (pinfunction "TP_1") (pintype "passive"))
    )
    (net (code "124") (name "USB_OTG1_VBUS") (class "Default")
      (node (ref "C807") (pin "1") (pinfunction "1_1") (pintype "passive"))
      (node (ref "C808") (pin "1") (pinfunction "1_1") (pintype "passive"))
      (node (ref "P801") (pin "13") (pinfunction "13_13") (pintype "passive"))
      (node (ref "TP809") (pin "1") (pinfunction "TP_1") (pintype "passive"))
    )
    (net (code "125") (name "USB_OTG2_DN") (class "Default")
      (node (ref "P801") (pin "21") (pinfunction "21_21") (pintype "passive"))
    )
    (net (code "126") (name "USB_OTG2_DP") (class "Default")
      (node (ref "P801") (pin "19") (pinfunction "19_19") (pintype "passive"))
    )
    (net (code "127") (name "USB_OTG2_VBUS") (class "Default")
      (node (ref "C805") (pin "1") (pinfunction "1_1") (pintype "passive"))
      (node (ref "C806") (pin "1") (pinfunction "1_1") (pintype "passive"))
      (node (ref "P801") (pin "11") (pinfunction "11_11") (pintype "passive"))
    )
    (net (code "128") (name "VDD_COIN_3V") (class "Default")
      (node (ref "C803") (pin "1") (pinfunction "1_1") (pintype "passive"))
      (node (ref "C804") (pin "1") (pinfunction "1_1") (pintype "passive"))
      (node (ref "P801") (pin "8") (pinfunction "8_8") (pintype "passive"))
    )
    (net (code "129") (name "VDD_SNVS_IN") (class "Default")
      (node (ref "C801") (pin "1") (pinfunction "1_1") (pintype "passive"))
      (node (ref "C802") (pin "1") (pinfunction "1_1") (pintype "passive"))
      (node (ref "P801") (pin "6") (pinfunction "6_6") (pintype "passive"))
      (node (ref "TP812") (pin "1") (pinfunction "TP_1") (pintype "passive"))
    )
    (net (code "130") (name "VSYS") (class "Default")
      (node (ref "C811") (pin "1") (pinfunction "1_1") (pintype "passive"))
      (node (ref "C812") (pin "1") (pinfunction "1_1") (pintype "passive"))
      (node (ref "C813") (pin "1") (pinfunction "1_1") (pintype "passive"))
      (node (ref "C814") (pin "1") (pinfunction "1_1") (pintype "passive"))
      (node (ref "P801") (pin "100") (pinfunction "100_100") (pintype "passive"))
      (node (ref "P801") (pin "102") (pinfunction "102_102") (pintype "passive"))
      (node (ref "P801") (pin "104") (pinfunction "104_104") (pintype "passive"))
      (node (ref "P801") (pin "106") (pinfunction "106_106") (pintype "passive"))
      (node (ref "P801") (pin "108") (pinfunction "108_108") (pintype "passive"))
      (node (ref "P801") (pin "110") (pinfunction "110_110") (pintype "passive"))
      (node (ref "P801") (pin "112") (pinfunction "112_112") (pintype "passive"))
      (node (ref "P801") (pin "96") (pinfunction "96_96") (pintype "passive"))
      (node (ref "P801") (pin "98") (pinfunction "98_98") (pintype "passive"))
      (node (ref "TP814") (pin "1") (pinfunction "TP_1") (pintype "passive"))
    )
    (net (code "131") (name "nUSB_OTG_CHD") (class "Default")
      (node (ref "P801") (pin "31") (pinfunction "31_31") (pintype "passive"))
    )
    (net (code "132") (name "unconnected-(P801-Pad83)") (class "Default")
      (node (ref "P801") (pin "83") (pinfunction "83_83") (pintype "passive"))
    )
    (net (code "133") (name "unconnected-(P801-Pad86)") (class "Default")
      (node (ref "P801") (pin "86") (pinfunction "86_86") (pintype "passive"))
    )
    (net (code "134") (name "unconnected-(P801-Pad94)") (class "Default")
      (node (ref "P801") (pin "94") (pinfunction "94_94") (pintype "passive"))
    )
    (net (code "135") (name "unconnected-(P801-Pad95)") (class "Default")
      (node (ref "P801") (pin "95") (pinfunction "95_95") (pintype "passive"))
    )
  )
)
